# fsr_endstop.net
KiCad netlist of a schematic drawn in EAGLE
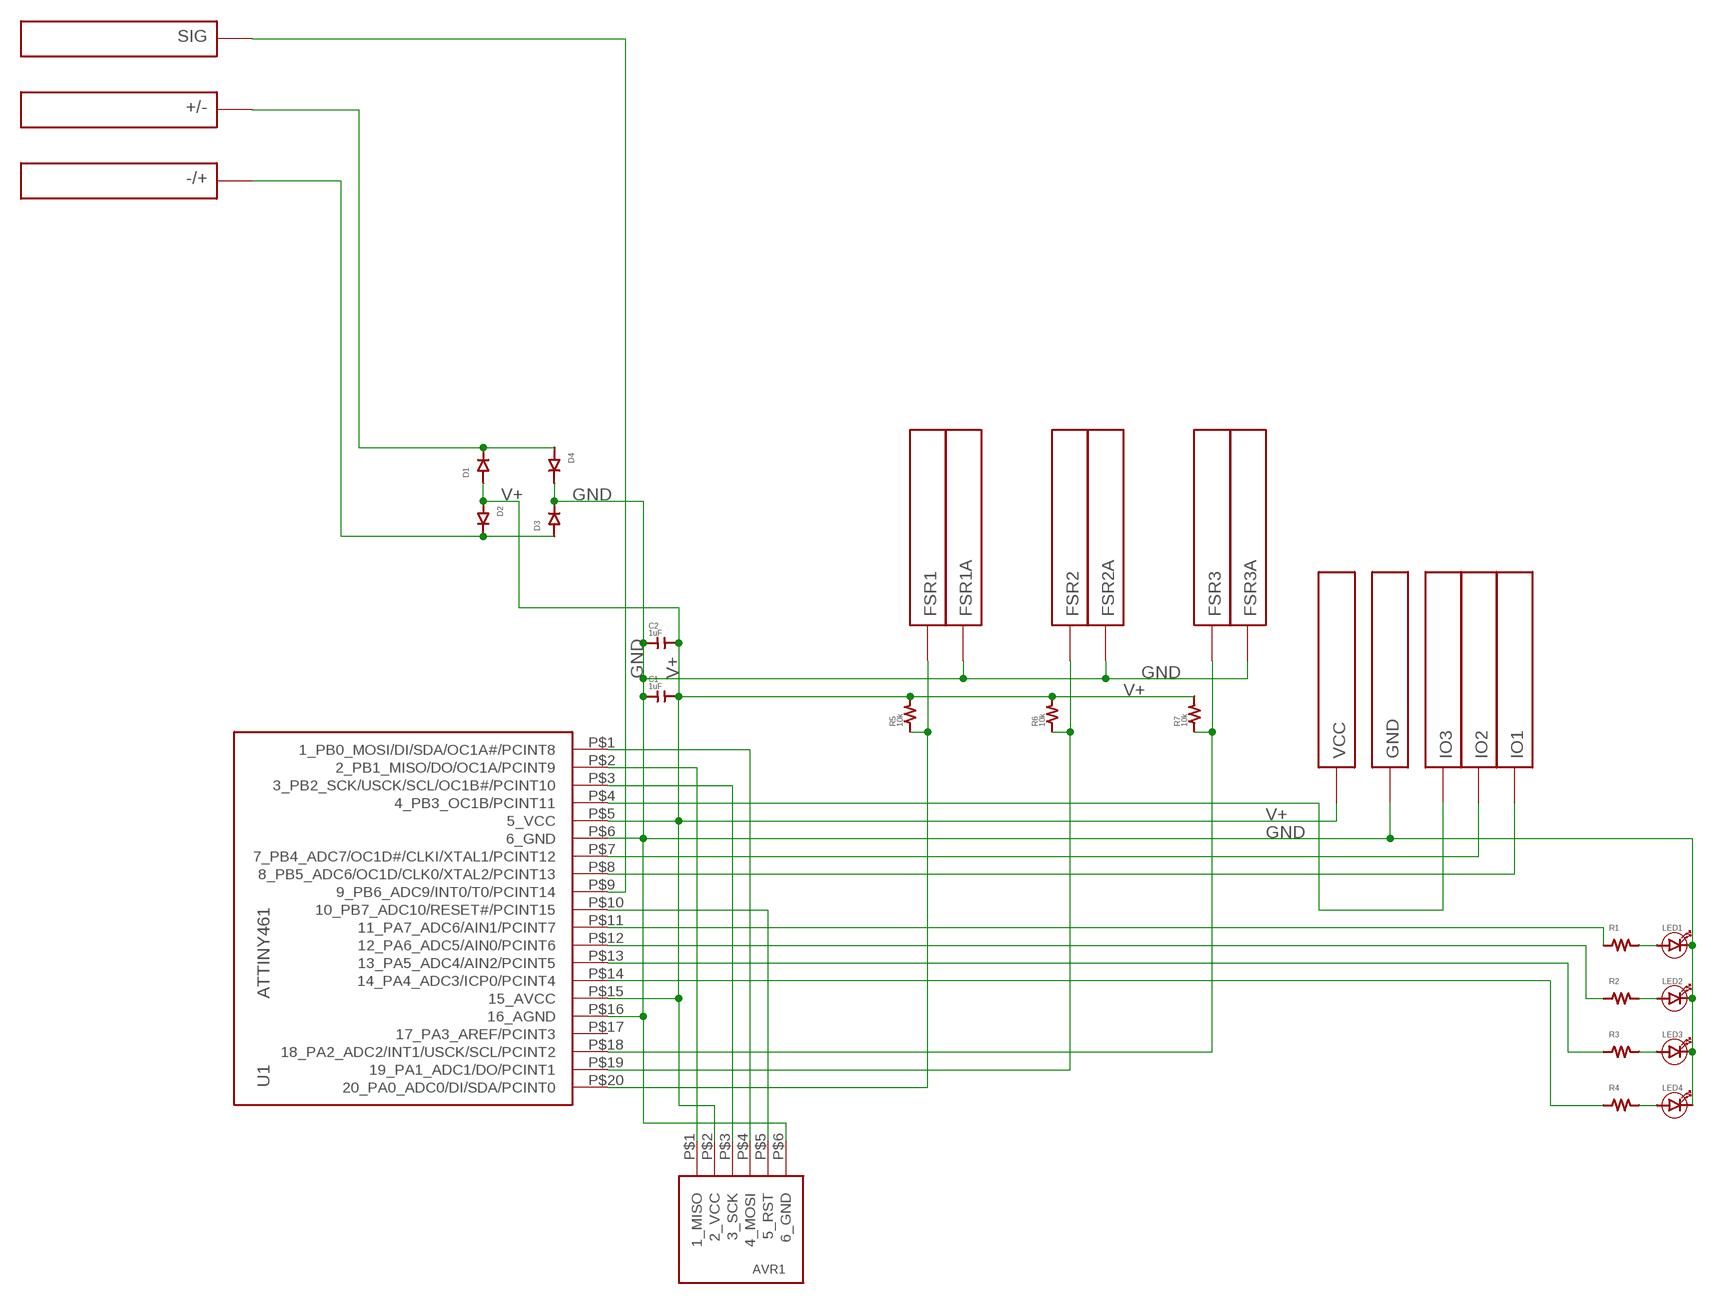
[diagram p0: schematic, sheet 1]

(export (version "E")
  (design (tool "Eeschema 10.0.6"))
  (components
    (comp (ref "+/-")
      (value "PIN1.2MM")
      (footprint "eagle-import:PIN_1.2MM")
      (libsource (lib "eagle-import") (part "PIN1.2MM"))
    )
    (comp (ref "-/+")
      (value "PIN1.2MM")
      (footprint "eagle-import:PIN_1.2MM")
      (libsource (lib "eagle-import") (part "PIN1.2MM"))
    )
    (comp (ref "AVR1")
      (value "AVR6")
      (footprint "eagle-import:AVR6")
      (libsource (lib "eagle-import") (part "AVR6"))
    )
    (comp (ref "C1")
      (value "1uF")
      (footprint "eagle-import:0603")
      (libsource (lib "eagle-import") (part "CAP0603"))
    )
    (comp (ref "C2")
      (value "1uF")
      (footprint "eagle-import:0603")
      (libsource (lib "eagle-import") (part "CAP0603"))
    )
    (comp (ref "D1")
      (value "DIODE0603")
      (footprint "eagle-import:0603_DIODE")
      (libsource (lib "eagle-import") (part "DIODE0603"))
    )
    (comp (ref "D2")
      (value "DIODE0603")
      (footprint "eagle-import:0603_DIODE")
      (libsource (lib "eagle-import") (part "DIODE0603"))
    )
    (comp (ref "D3")
      (value "DIODE0603")
      (footprint "eagle-import:0603_DIODE")
      (libsource (lib "eagle-import") (part "DIODE0603"))
    )
    (comp (ref "D4")
      (value "DIODE0603")
      (footprint "eagle-import:0603_DIODE")
      (libsource (lib "eagle-import") (part "DIODE0603"))
    )
    (comp (ref "FSR1")
      (value "PIN1.2MM")
      (footprint "eagle-import:PIN_1.2MM")
      (libsource (lib "eagle-import") (part "PIN1.2MM"))
    )
    (comp (ref "FSR1A")
      (value "PIN1.2MM")
      (footprint "eagle-import:PIN_1.2MM")
      (libsource (lib "eagle-import") (part "PIN1.2MM"))
    )
    (comp (ref "FSR2")
      (value "PIN1.2MM")
      (footprint "eagle-import:PIN_1.2MM")
      (libsource (lib "eagle-import") (part "PIN1.2MM"))
    )
    (comp (ref "FSR2A")
      (value "PIN1.2MM")
      (footprint "eagle-import:PIN_1.2MM")
      (libsource (lib "eagle-import") (part "PIN1.2MM"))
    )
    (comp (ref "FSR3")
      (value "PIN1.2MM")
      (footprint "eagle-import:PIN_1.2MM")
      (libsource (lib "eagle-import") (part "PIN1.2MM"))
    )
    (comp (ref "FSR3A")
      (value "PIN1.2MM")
      (footprint "eagle-import:PIN_1.2MM")
      (libsource (lib "eagle-import") (part "PIN1.2MM"))
    )
    (comp (ref "GND")
      (value "PIN1.2MM")
      (footprint "eagle-import:PIN_1.2MM")
      (libsource (lib "eagle-import") (part "PIN1.2MM"))
    )
    (comp (ref "IO1")
      (value "PIN1.2MM")
      (footprint "eagle-import:PIN_1.2MM")
      (libsource (lib "eagle-import") (part "PIN1.2MM"))
    )
    (comp (ref "IO2")
      (value "PIN1.2MM")
      (footprint "eagle-import:PIN_1.2MM")
      (libsource (lib "eagle-import") (part "PIN1.2MM"))
    )
    (comp (ref "IO3")
      (value "PIN1.2MM")
      (footprint "eagle-import:PIN_1.2MM")
      (libsource (lib "eagle-import") (part "PIN1.2MM"))
    )
    (comp (ref "LED1")
      (value "LED0603")
      (footprint "eagle-import:0603_DIODE")
      (libsource (lib "eagle-import") (part "LED0603"))
    )
    (comp (ref "LED2")
      (value "LED0603")
      (footprint "eagle-import:0603_DIODE")
      (libsource (lib "eagle-import") (part "LED0603"))
    )
    (comp (ref "LED3")
      (value "LED0603")
      (footprint "eagle-import:0603_DIODE")
      (libsource (lib "eagle-import") (part "LED0603"))
    )
    (comp (ref "LED4")
      (value "LED0603")
      (footprint "eagle-import:0603_DIODE")
      (libsource (lib "eagle-import") (part "LED0603"))
    )
    (comp (ref "R1")
      (value "RES0603")
      (footprint "eagle-import:0603")
      (libsource (lib "eagle-import") (part "RES0603"))
    )
    (comp (ref "R2")
      (value "RES0603")
      (footprint "eagle-import:0603")
      (libsource (lib "eagle-import") (part "RES0603"))
    )
    (comp (ref "R3")
      (value "RES0603")
      (footprint "eagle-import:0603")
      (libsource (lib "eagle-import") (part "RES0603"))
    )
    (comp (ref "R4")
      (value "RES0603")
      (footprint "eagle-import:0603")
      (libsource (lib "eagle-import") (part "RES0603"))
    )
    (comp (ref "R5")
      (value "10k")
      (footprint "eagle-import:0603")
      (libsource (lib "eagle-import") (part "RES0603"))
    )
    (comp (ref "R6")
      (value "10k")
      (footprint "eagle-import:0603")
      (libsource (lib "eagle-import") (part "RES0603"))
    )
    (comp (ref "R7")
      (value "10k")
      (footprint "eagle-import:0603")
      (libsource (lib "eagle-import") (part "RES0603"))
    )
    (comp (ref "SIG")
      (value "PIN1.2MM")
      (footprint "eagle-import:PIN_1.2MM")
      (libsource (lib "eagle-import") (part "PIN1.2MM"))
    )
    (comp (ref "U1")
      (value "ATTINY461")
      (footprint "eagle-import:SOIC-20")
      (libsource (lib "eagle-import") (part "ATTINY461"))
    )
    (comp (ref "VCC")
      (value "PIN1.2MM")
      (footprint "eagle-import:PIN_1.2MM")
      (libsource (lib "eagle-import") (part "PIN1.2MM"))
    )
  )
  (nets
    (net (code "1") (name "/GND") (class "Default")
      (node (ref "AVR1") (pin "P$6") (pinfunction "6_GND_P$6") (pintype "bidirectional"))
      (node (ref "C1") (pin "1") (pinfunction "P$1_1") (pintype "bidirectional"))
      (node (ref "C2") (pin "1") (pinfunction "P$1_1") (pintype "bidirectional"))
      (node (ref "D3") (pin "-") (pinfunction "-_-") (pintype "bidirectional"))
      (node (ref "D4") (pin "-") (pinfunction "-_-") (pintype "bidirectional"))
      (node (ref "FSR1A") (pin "P$1") (pinfunction "P$1_P$1") (pintype "bidirectional"))
      (node (ref "FSR2A") (pin "P$1") (pinfunction "P$1_P$1") (pintype "bidirectional"))
      (node (ref "FSR3A") (pin "P$1") (pinfunction "P$1_P$1") (pintype "bidirectional"))
      (node (ref "GND") (pin "P$1") (pinfunction "P$1_P$1") (pintype "bidirectional"))
      (node (ref "LED1") (pin "-") (pinfunction "-_-") (pintype "bidirectional"))
      (node (ref "LED2") (pin "-") (pinfunction "-_-") (pintype "bidirectional"))
      (node (ref "LED3") (pin "-") (pinfunction "-_-") (pintype "bidirectional"))
      (node (ref "LED4") (pin "-") (pinfunction "-_-") (pintype "bidirectional"))
      (node (ref "U1") (pin "P$16") (pinfunction "16_AGND_P$16") (pintype "bidirectional"))
      (node (ref "U1") (pin "P$6") (pinfunction "6_GND_P$6") (pintype "bidirectional"))
    )
    (net (code "2") (name "/V+") (class "Default")
      (node (ref "AVR1") (pin "P$2") (pinfunction "2_VCC_P$2") (pintype "bidirectional"))
      (node (ref "C1") (pin "2") (pinfunction "P$2_2") (pintype "bidirectional"))
      (node (ref "C2") (pin "2") (pinfunction "P$2_2") (pintype "bidirectional"))
      (node (ref "D1") (pin "+") (pinfunction "+_+") (pintype "bidirectional"))
      (node (ref "D2") (pin "+") (pinfunction "+_+") (pintype "bidirectional"))
      (node (ref "R5") (pin "2") (pinfunction "P$2_2") (pintype "bidirectional"))
      (node (ref "R6") (pin "2") (pinfunction "P$2_2") (pintype "bidirectional"))
      (node (ref "R7") (pin "2") (pinfunction "P$2_2") (pintype "bidirectional"))
      (node (ref "U1") (pin "P$15") (pinfunction "15_AVCC_P$15") (pintype "bidirectional"))
      (node (ref "U1") (pin "P$5") (pinfunction "5_VCC_P$5") (pintype "bidirectional"))
      (node (ref "VCC") (pin "P$1") (pinfunction "P$1_P$1") (pintype "bidirectional"))
    )
    (net (code "3") (name "Net-(+/--PadP$1)") (class "Default")
      (node (ref "+/-") (pin "P$1") (pinfunction "P$1_P$1") (pintype "bidirectional"))
      (node (ref "D1") (pin "-") (pinfunction "-_-") (pintype "bidirectional"))
      (node (ref "D4") (pin "+") (pinfunction "+_+") (pintype "bidirectional"))
    )
    (net (code "4") (name "Net-(-/+-PadP$1)") (class "Default")
      (node (ref "-/+") (pin "P$1") (pinfunction "P$1_P$1") (pintype "bidirectional"))
      (node (ref "D2") (pin "-") (pinfunction "-_-") (pintype "bidirectional"))
      (node (ref "D3") (pin "+") (pinfunction "+_+") (pintype "bidirectional"))
    )
    (net (code "5") (name "Net-(AVR1-1_MISO)") (class "Default")
      (node (ref "AVR1") (pin "P$1") (pinfunction "1_MISO_P$1") (pintype "bidirectional"))
      (node (ref "U1") (pin "P$2") (pinfunction "2_PB1_MISO/DO/OC1A/PCINT9_P$2") (pintype "bidirectional"))
    )
    (net (code "6") (name "Net-(AVR1-3_SCK)") (class "Default")
      (node (ref "AVR1") (pin "P$3") (pinfunction "3_SCK_P$3") (pintype "bidirectional"))
      (node (ref "U1") (pin "P$3") (pinfunction "3_PB2_SCK/USCK/SCL/OC1B#/PCINT10_P$3") (pintype "bidirectional"))
    )
    (net (code "7") (name "Net-(AVR1-4_MOSI)") (class "Default")
      (node (ref "AVR1") (pin "P$4") (pinfunction "4_MOSI_P$4") (pintype "bidirectional"))
      (node (ref "U1") (pin "P$1") (pinfunction "1_PB0_MOSI/DI/SDA/OC1A#/PCINT8_P$1") (pintype "bidirectional"))
    )
    (net (code "8") (name "Net-(AVR1-5_RST)") (class "Default")
      (node (ref "AVR1") (pin "P$5") (pinfunction "5_RST_P$5") (pintype "bidirectional"))
      (node (ref "U1") (pin "P$10") (pinfunction "10_PB7_ADC10/RESET#/PCINT15_P$10") (pintype "bidirectional"))
    )
    (net (code "9") (name "Net-(R1-P$1)") (class "Default")
      (node (ref "R1") (pin "1") (pinfunction "P$1_1") (pintype "bidirectional"))
      (node (ref "U1") (pin "P$11") (pinfunction "11_PA7_ADC6/AIN1/PCINT7_P$11") (pintype "bidirectional"))
    )
    (net (code "10") (name "Net-(R1-P$2)") (class "Default")
      (node (ref "LED1") (pin "+") (pinfunction "+_+") (pintype "bidirectional"))
      (node (ref "R1") (pin "2") (pinfunction "P$2_2") (pintype "bidirectional"))
    )
    (net (code "11") (name "Net-(R2-P$1)") (class "Default")
      (node (ref "R2") (pin "1") (pinfunction "P$1_1") (pintype "bidirectional"))
      (node (ref "U1") (pin "P$12") (pinfunction "12_PA6_ADC5/AIN0/PCINT6_P$12") (pintype "bidirectional"))
    )
    (net (code "12") (name "Net-(R2-P$2)") (class "Default")
      (node (ref "LED2") (pin "+") (pinfunction "+_+") (pintype "bidirectional"))
      (node (ref "R2") (pin "2") (pinfunction "P$2_2") (pintype "bidirectional"))
    )
    (net (code "13") (name "Net-(R3-P$1)") (class "Default")
      (node (ref "R3") (pin "1") (pinfunction "P$1_1") (pintype "bidirectional"))
      (node (ref "U1") (pin "P$13") (pinfunction "13_PA5_ADC4/AIN2/PCINT5_P$13") (pintype "bidirectional"))
    )
    (net (code "14") (name "Net-(R3-P$2)") (class "Default")
      (node (ref "LED3") (pin "+") (pinfunction "+_+") (pintype "bidirectional"))
      (node (ref "R3") (pin "2") (pinfunction "P$2_2") (pintype "bidirectional"))
    )
    (net (code "15") (name "Net-(R4-P$1)") (class "Default")
      (node (ref "R4") (pin "1") (pinfunction "P$1_1") (pintype "bidirectional"))
      (node (ref "U1") (pin "P$14") (pinfunction "14_PA4_ADC3/ICP0/PCINT4_P$14") (pintype "bidirectional"))
    )
    (net (code "16") (name "Net-(R4-P$2)") (class "Default")
      (node (ref "LED4") (pin "+") (pinfunction "+_+") (pintype "bidirectional"))
      (node (ref "R4") (pin "2") (pinfunction "P$2_2") (pintype "bidirectional"))
    )
    (net (code "17") (name "Net-(R5-P$1)") (class "Default")
      (node (ref "FSR1") (pin "P$1") (pinfunction "P$1_P$1") (pintype "bidirectional"))
      (node (ref "R5") (pin "1") (pinfunction "P$1_1") (pintype "bidirectional"))
      (node (ref "U1") (pin "P$20") (pinfunction "20_PA0_ADC0/DI/SDA/PCINT0_P$20") (pintype "bidirectional"))
    )
    (net (code "18") (name "Net-(R6-P$1)") (class "Default")
      (node (ref "FSR2") (pin "P$1") (pinfunction "P$1_P$1") (pintype "bidirectional"))
      (node (ref "R6") (pin "1") (pinfunction "P$1_1") (pintype "bidirectional"))
      (node (ref "U1") (pin "P$19") (pinfunction "19_PA1_ADC1/DO/PCINT1_P$19") (pintype "bidirectional"))
    )
    (net (code "19") (name "Net-(R7-P$1)") (class "Default")
      (node (ref "FSR3") (pin "P$1") (pinfunction "P$1_P$1") (pintype "bidirectional"))
      (node (ref "R7") (pin "1") (pinfunction "P$1_1") (pintype "bidirectional"))
      (node (ref "U1") (pin "P$18") (pinfunction "18_PA2_ADC2/INT1/USCK/SCL/PCINT2_P$18") (pintype "bidirectional"))
    )
    (net (code "20") (name "Net-(U1-4_PB3_OC1B{slash}PCINT11)") (class "Default")
      (node (ref "IO3") (pin "P$1") (pinfunction "P$1_P$1") (pintype "bidirectional"))
      (node (ref "U1") (pin "P$4") (pinfunction "4_PB3_OC1B/PCINT11_P$4") (pintype "bidirectional"))
    )
    (net (code "21") (name "Net-(U1-7_PB4_ADC7{slash}OC1D#{slash}CLKI{slash}XTAL1{slash}PCINT12)") (class "Default")
      (node (ref "IO2") (pin "P$1") (pinfunction "P$1_P$1") (pintype "bidirectional"))
      (node (ref "U1") (pin "P$7") (pinfunction "7_PB4_ADC7/OC1D#/CLKI/XTAL1/PCINT12_P$7") (pintype "bidirectional"))
    )
    (net (code "22") (name "Net-(U1-8_PB5_ADC6{slash}OC1D{slash}CLK0{slash}XTAL2{slash}PCINT13)") (class "Default")
      (node (ref "IO1") (pin "P$1") (pinfunction "P$1_P$1") (pintype "bidirectional"))
      (node (ref "U1") (pin "P$8") (pinfunction "8_PB5_ADC6/OC1D/CLK0/XTAL2/PCINT13_P$8") (pintype "bidirectional"))
    )
    (net (code "23") (name "Net-(U1-9_PB6_ADC9{slash}INT0{slash}T0{slash}PCINT14)") (class "Default")
      (node (ref "SIG") (pin "P$1") (pinfunction "P$1_P$1") (pintype "bidirectional"))
      (node (ref "U1") (pin "P$9") (pinfunction "9_PB6_ADC9/INT0/T0/PCINT14_P$9") (pintype "bidirectional"))
    )
    (net (code "24") (name "unconnected-(U1-17_PA3_AREF{slash}PCINT3-PadP$17)") (class "Default")
      (node (ref "U1") (pin "P$17") (pinfunction "17_PA3_AREF/PCINT3_P$17") (pintype "bidirectional"))
    )
  )
)
